# ATtiny84LEDEL.net
KiCad netlist of a schematic drawn in EAGLE
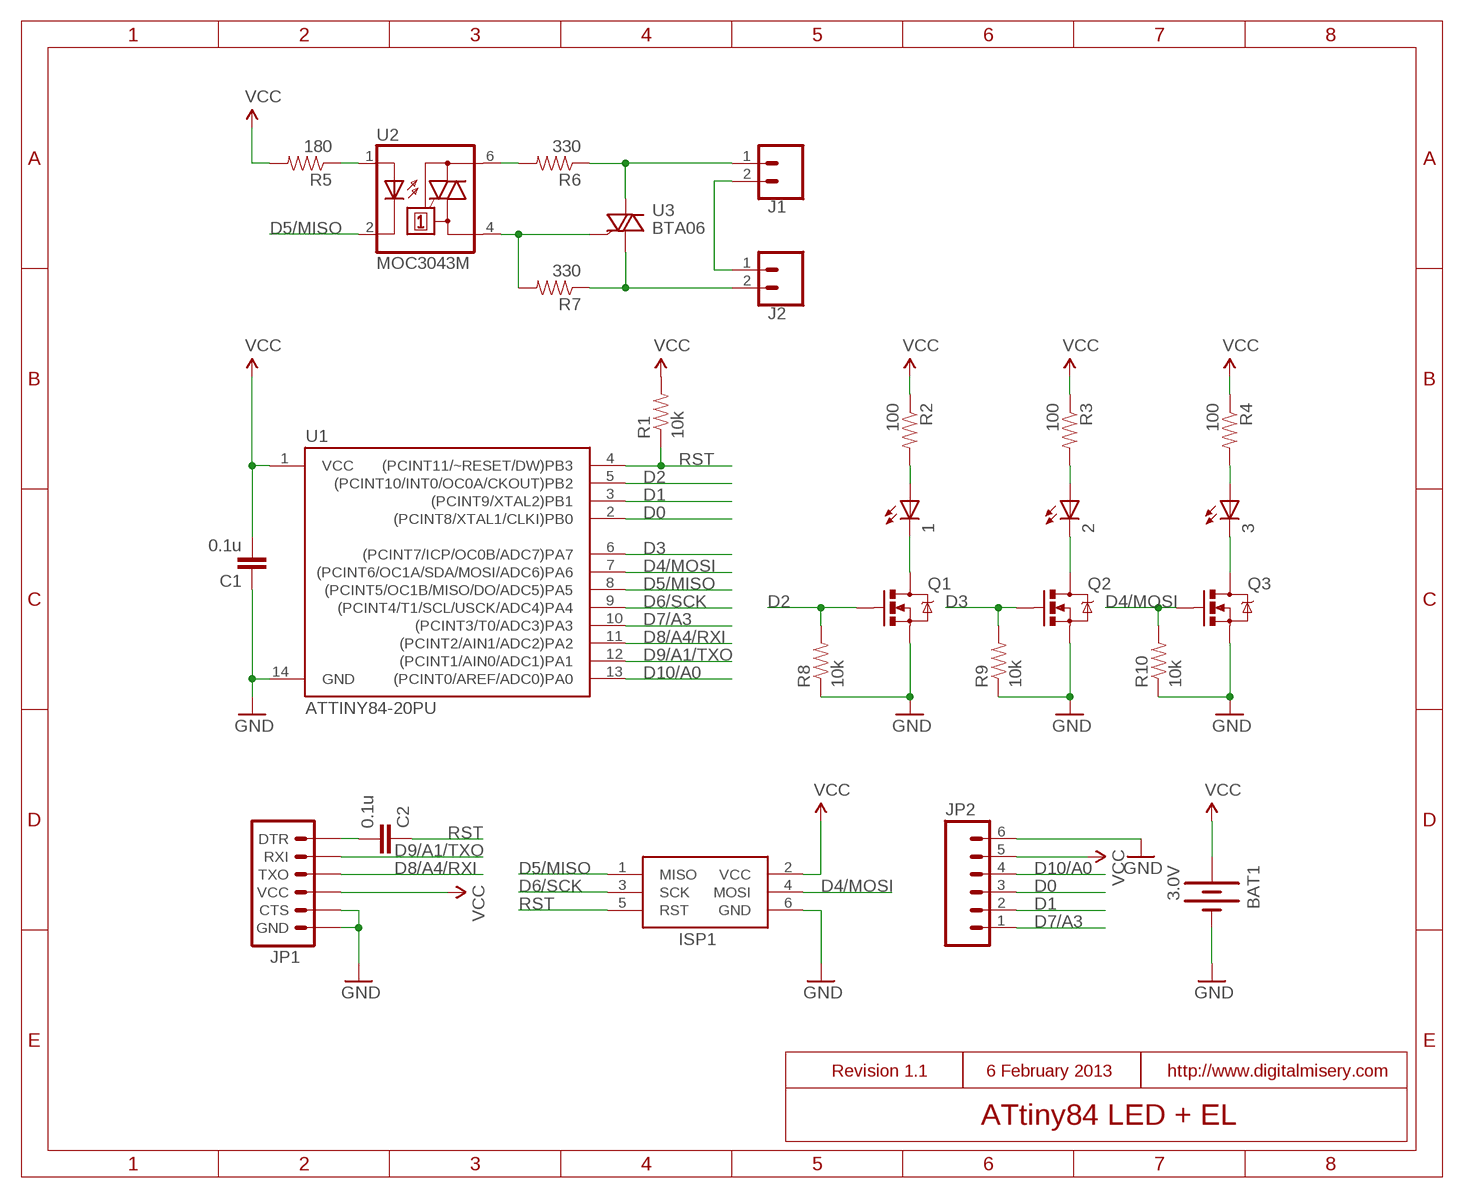
[diagram p0: schematic, sheet 1]

(export (version "E")
  (design (tool "Eeschema 10.0.6"))
  (components
    (comp (ref "1")
      (value "LED5MM")
      (footprint "eagle-import:LED5MM")
      (libsource (lib "eagle-import") (part "LED5MM"))
    )
    (comp (ref "2")
      (value "LED5MM")
      (footprint "eagle-import:LED5MM")
      (libsource (lib "eagle-import") (part "LED5MM"))
    )
    (comp (ref "3")
      (value "LED5MM")
      (footprint "eagle-import:LED5MM")
      (libsource (lib "eagle-import") (part "LED5MM"))
    )
    (comp (ref "BAT1")
      (value "3.0V")
      (footprint "eagle-import:JEELABS_BATTCOM_20MM_PTH")
      (libsource (lib "eagle-import") (part "JEELABS_BATTERY20PTH"))
    )
    (comp (ref "C1")
      (value "0.1u")
      (footprint "eagle-import:CAP-PTH-SMALL")
      (libsource (lib "eagle-import") (part "CAPPTH"))
    )
    (comp (ref "C2")
      (value "0.1u")
      (footprint "eagle-import:CAP-PTH-SMALL")
      (libsource (lib "eagle-import") (part "CAPPTH"))
    )
    (comp (ref "ISP1")
      (value "AVRISP-6")
      (footprint "eagle-import:AVRISP")
      (libsource (lib "eagle-import") (part "AVRISP-6"))
    )
    (comp (ref "J1")
      (value "M025MM")
      (footprint "eagle-import:SCREWTERMINAL-5MM-2")
      (libsource (lib "eagle-import") (part "M025MM"))
    )
    (comp (ref "J2")
      (value "M025MM")
      (footprint "eagle-import:SCREWTERMINAL-5MM-2")
      (libsource (lib "eagle-import") (part "M025MM"))
    )
    (comp (ref "JP1")
      (value "ARDUINO_SERIAL_PROGRAMLONGPADS")
      (footprint "eagle-import:1X06_LONGPADS")
      (libsource (lib "eagle-import") (part "ARDUINO_SERIAL_PROGRAMLONGPADS"))
    )
    (comp (ref "JP2")
      (value "M06LONGPADS")
      (footprint "eagle-import:1X06_LONGPADS")
      (libsource (lib "eagle-import") (part "M06LONGPADS"))
    )
    (comp (ref "Q1")
      (value "MOSFET-NCHANNELPTH")
      (footprint "eagle-import:TO-92")
      (libsource (lib "eagle-import") (part "MOSFET-NCHANNELPTH"))
    )
    (comp (ref "Q2")
      (value "MOSFET-NCHANNELPTH")
      (footprint "eagle-import:TO-92")
      (libsource (lib "eagle-import") (part "MOSFET-NCHANNELPTH"))
    )
    (comp (ref "Q3")
      (value "MOSFET-NCHANNELPTH")
      (footprint "eagle-import:TO-92")
      (libsource (lib "eagle-import") (part "MOSFET-NCHANNELPTH"))
    )
    (comp (ref "R1")
      (value "10k")
      (footprint "eagle-import:AXIAL-0.4")
      (libsource (lib "eagle-import") (part "RESISTORPTH-1/4W"))
    )
    (comp (ref "R2")
      (value "100")
      (footprint "eagle-import:AXIAL-0.4")
      (libsource (lib "eagle-import") (part "RESISTORPTH-1/4W"))
    )
    (comp (ref "R3")
      (value "100")
      (footprint "eagle-import:AXIAL-0.4")
      (libsource (lib "eagle-import") (part "RESISTORPTH-1/4W"))
    )
    (comp (ref "R4")
      (value "100")
      (footprint "eagle-import:AXIAL-0.4")
      (libsource (lib "eagle-import") (part "RESISTORPTH-1/4W"))
    )
    (comp (ref "R5")
      (value "180")
      (footprint "eagle-import:AXIAL-0.4")
      (libsource (lib "eagle-import") (part "RESISTORPTH-1/4W"))
    )
    (comp (ref "R6")
      (value "330")
      (footprint "eagle-import:AXIAL-0.4")
      (libsource (lib "eagle-import") (part "RESISTORPTH-1/4W"))
    )
    (comp (ref "R7")
      (value "330")
      (footprint "eagle-import:AXIAL-0.4")
      (libsource (lib "eagle-import") (part "RESISTORPTH-1/4W"))
    )
    (comp (ref "R8")
      (value "10k")
      (footprint "eagle-import:AXIAL-0.4")
      (libsource (lib "eagle-import") (part "RESISTORPTH-1/4W"))
    )
    (comp (ref "R9")
      (value "10k")
      (footprint "eagle-import:AXIAL-0.4")
      (libsource (lib "eagle-import") (part "RESISTORPTH-1/4W"))
    )
    (comp (ref "R10")
      (value "10k")
      (footprint "eagle-import:AXIAL-0.4")
      (libsource (lib "eagle-import") (part "RESISTORPTH-1/4W"))
    )
    (comp (ref "U1")
      (value "ATTINY84-20PU")
      (footprint "eagle-import:DIL14")
      (libsource (lib "eagle-import") (part "ATTINY84ATTINY84-20PU"))
    )
    (comp (ref "U2")
      (value "MOC3043M")
      (footprint "eagle-import:DIL06")
      (fields (field (name "MF") "FAIRCHILD SEMICONDUCTOR") (field (name "MPN") "MOC3043-M"))
      (libsource (lib "eagle-import") (part "MOC3043M"))
    )
    (comp (ref "U3")
      (value "BTA06")
      (footprint "eagle-import:TO220AB")
      (libsource (lib "eagle-import") (part "BTA06"))
    )
  )
  (nets
    (net (code "1") (name "/D0") (class "Default")
      (node (ref "JP2") (pin "3") (pinfunction "3_3") (pintype "passive"))
      (node (ref "U1") (pin "2") (pinfunction "(PCINT8/XTAL1/CLKI)PB0_2") (pintype "bidirectional"))
    )
    (net (code "2") (name "/D1") (class "Default")
      (node (ref "JP2") (pin "2") (pinfunction "2_2") (pintype "passive"))
      (node (ref "U1") (pin "3") (pinfunction "(PCINT9/XTAL2)PB1_3") (pintype "bidirectional"))
    )
    (net (code "3") (name "/D2") (class "Default")
      (node (ref "Q1") (pin "2") (pinfunction "G_2") (pintype "passive"))
      (node (ref "R8") (pin "P$2") (pinfunction "2_P$2") (pintype "passive"))
      (node (ref "U1") (pin "5") (pinfunction "(PCINT10/INT0/OC0A/CKOUT)PB2_5") (pintype "bidirectional"))
    )
    (net (code "4") (name "/D3") (class "Default")
      (node (ref "Q2") (pin "2") (pinfunction "G_2") (pintype "passive"))
      (node (ref "R9") (pin "P$2") (pinfunction "2_P$2") (pintype "passive"))
      (node (ref "U1") (pin "6") (pinfunction "(PCINT7/ICP/OC0B/ADC7)PA7_6") (pintype "bidirectional"))
    )
    (net (code "5") (name "/D4{slash}MOSI") (class "Default")
      (node (ref "ISP1") (pin "4") (pinfunction "MOSI_4") (pintype "output"))
      (node (ref "Q3") (pin "2") (pinfunction "G_2") (pintype "passive"))
      (node (ref "R10") (pin "P$2") (pinfunction "2_P$2") (pintype "passive"))
      (node (ref "U1") (pin "7") (pinfunction "(PCINT6/OC1A/SDA/MOSI/ADC6)PA6_7") (pintype "bidirectional"))
    )
    (net (code "6") (name "/D5{slash}MISO") (class "Default")
      (node (ref "ISP1") (pin "1") (pinfunction "MISO_1") (pintype "input"))
      (node (ref "U1") (pin "8") (pinfunction "(PCINT5/OC1B/MISO/DO/ADC5)PA5_8") (pintype "bidirectional"))
      (node (ref "U2") (pin "2") (pinfunction "C_2") (pintype "passive"))
    )
    (net (code "7") (name "/D6{slash}SCK") (class "Default")
      (node (ref "ISP1") (pin "3") (pinfunction "SCK_3") (pintype "output"))
      (node (ref "U1") (pin "9") (pinfunction "(PCINT4/T1/SCL/USCK/ADC4)PA4_9") (pintype "bidirectional"))
    )
    (net (code "8") (name "/D7{slash}A3") (class "Default")
      (node (ref "JP2") (pin "1") (pinfunction "1_1") (pintype "passive"))
      (node (ref "U1") (pin "10") (pinfunction "(PCINT3/T0/ADC3)PA3_10") (pintype "bidirectional"))
    )
    (net (code "9") (name "/D8{slash}A4{slash}RXI") (class "Default")
      (node (ref "JP1") (pin "3") (pinfunction "TXO_3") (pintype "passive"))
      (node (ref "U1") (pin "11") (pinfunction "(PCINT2/AIN1/ADC2)PA2_11") (pintype "bidirectional"))
    )
    (net (code "10") (name "/D9{slash}A1{slash}TXO") (class "Default")
      (node (ref "JP1") (pin "2") (pinfunction "RXI_2") (pintype "passive"))
      (node (ref "U1") (pin "12") (pinfunction "(PCINT1/AIN0/ADC1)PA1_12") (pintype "bidirectional"))
    )
    (net (code "11") (name "/D10{slash}A0") (class "Default")
      (node (ref "JP2") (pin "4") (pinfunction "4_4") (pintype "passive"))
      (node (ref "U1") (pin "13") (pinfunction "(PCINT0/AREF/ADC0)PA0_13") (pintype "bidirectional"))
    )
    (net (code "12") (name "/RST") (class "Default")
      (node (ref "C2") (pin "1") (pinfunction "1_1") (pintype "passive"))
      (node (ref "ISP1") (pin "5") (pinfunction "RST_5") (pintype "output"))
      (node (ref "R1") (pin "P$1") (pinfunction "1_P$1") (pintype "passive"))
      (node (ref "U1") (pin "4") (pinfunction "(PCINT11/~{RESET/DW})PB3_4") (pintype "bidirectional"))
    )
    (net (code "13") (name "GND") (class "Default")
      (node (ref "BAT1") (pin "2") (pinfunction "-_2") (pintype "power_in"))
      (node (ref "C1") (pin "1") (pinfunction "1_1") (pintype "passive"))
      (node (ref "ISP1") (pin "6") (pinfunction "GND_6") (pintype "power_in"))
      (node (ref "JP1") (pin "5") (pinfunction "CTS_5") (pintype "passive"))
      (node (ref "JP1") (pin "6") (pinfunction "GND_6") (pintype "passive"))
      (node (ref "JP2") (pin "6") (pinfunction "6_6") (pintype "passive"))
      (node (ref "Q1") (pin "3") (pinfunction "S_3") (pintype "passive"))
      (node (ref "Q2") (pin "3") (pinfunction "S_3") (pintype "passive"))
      (node (ref "Q3") (pin "3") (pinfunction "S_3") (pintype "passive"))
      (node (ref "R10") (pin "P$1") (pinfunction "1_P$1") (pintype "passive"))
      (node (ref "R8") (pin "P$1") (pinfunction "1_P$1") (pintype "passive"))
      (node (ref "R9") (pin "P$1") (pinfunction "1_P$1") (pintype "passive"))
      (node (ref "U1") (pin "14") (pinfunction "GND_14") (pintype "bidirectional"))
    )
    (net (code "14") (name "Net-(1-C)") (class "Default")
      (node (ref "1") (pin "K") (pinfunction "C_K") (pintype "passive"))
      (node (ref "Q1") (pin "1") (pinfunction "D_1") (pintype "passive"))
    )
    (net (code "15") (name "Net-(2-C)") (class "Default")
      (node (ref "2") (pin "K") (pinfunction "C_K") (pintype "passive"))
      (node (ref "Q2") (pin "1") (pinfunction "D_1") (pintype "passive"))
    )
    (net (code "16") (name "Net-(3-C)") (class "Default")
      (node (ref "3") (pin "K") (pinfunction "C_K") (pintype "passive"))
      (node (ref "Q3") (pin "1") (pinfunction "D_1") (pintype "passive"))
    )
    (net (code "17") (name "Net-(J1-Pad2)") (class "Default")
      (node (ref "J1") (pin "2") (pinfunction "2_2") (pintype "passive"))
      (node (ref "J2") (pin "1") (pinfunction "1_1") (pintype "passive"))
    )
    (net (code "18") (name "Net-(JP1-DTR)") (class "Default")
      (node (ref "C2") (pin "2") (pinfunction "2_2") (pintype "passive"))
      (node (ref "JP1") (pin "1") (pinfunction "DTR_1") (pintype "passive"))
    )
    (net (code "19") (name "Net-(R2-2)") (class "Default")
      (node (ref "1") (pin "A") (pinfunction "A_A") (pintype "passive"))
      (node (ref "R2") (pin "P$2") (pinfunction "2_P$2") (pintype "passive"))
    )
    (net (code "20") (name "Net-(R3-2)") (class "Default")
      (node (ref "2") (pin "A") (pinfunction "A_A") (pintype "passive"))
      (node (ref "R3") (pin "P$2") (pinfunction "2_P$2") (pintype "passive"))
    )
    (net (code "21") (name "Net-(R4-2)") (class "Default")
      (node (ref "3") (pin "A") (pinfunction "A_A") (pintype "passive"))
      (node (ref "R4") (pin "P$2") (pinfunction "2_P$2") (pintype "passive"))
    )
    (net (code "22") (name "Net-(R5-1)") (class "Default")
      (node (ref "R5") (pin "P$1") (pinfunction "1_P$1") (pintype "passive"))
      (node (ref "U2") (pin "1") (pinfunction "A_1") (pintype "passive"))
    )
    (net (code "23") (name "Net-(R6-1)") (class "Default")
      (node (ref "J1") (pin "1") (pinfunction "1_1") (pintype "passive"))
      (node (ref "R6") (pin "P$1") (pinfunction "1_P$1") (pintype "passive"))
      (node (ref "U3") (pin "2") (pinfunction "A2_2") (pintype "passive"))
    )
    (net (code "24") (name "Net-(R6-2)") (class "Default")
      (node (ref "R6") (pin "P$2") (pinfunction "2_P$2") (pintype "passive"))
      (node (ref "U2") (pin "6") (pinfunction "A2_6") (pintype "passive"))
    )
    (net (code "25") (name "Net-(R7-1)") (class "Default")
      (node (ref "J2") (pin "2") (pinfunction "2_2") (pintype "passive"))
      (node (ref "R7") (pin "P$1") (pinfunction "1_P$1") (pintype "passive"))
      (node (ref "U3") (pin "1") (pinfunction "A1_1") (pintype "passive"))
    )
    (net (code "26") (name "Net-(R7-2)") (class "Default")
      (node (ref "R7") (pin "P$2") (pinfunction "2_P$2") (pintype "passive"))
      (node (ref "U2") (pin "4") (pinfunction "A1_4") (pintype "passive"))
      (node (ref "U3") (pin "3") (pinfunction "G_3") (pintype "passive"))
    )
    (net (code "27") (name "VCC") (class "Default")
      (node (ref "BAT1") (pin "1") (pinfunction "+_1") (pintype "power_in"))
      (node (ref "C1") (pin "2") (pinfunction "2_2") (pintype "passive"))
      (node (ref "ISP1") (pin "2") (pinfunction "VCC_2") (pintype "power_in"))
      (node (ref "JP1") (pin "4") (pinfunction "VCC_4") (pintype "passive"))
      (node (ref "JP2") (pin "5") (pinfunction "5_5") (pintype "passive"))
      (node (ref "R1") (pin "P$2") (pinfunction "2_P$2") (pintype "passive"))
      (node (ref "R2") (pin "P$1") (pinfunction "1_P$1") (pintype "passive"))
      (node (ref "R3") (pin "P$1") (pinfunction "1_P$1") (pintype "passive"))
      (node (ref "R4") (pin "P$1") (pinfunction "1_P$1") (pintype "passive"))
      (node (ref "R5") (pin "P$2") (pinfunction "2_P$2") (pintype "passive"))
      (node (ref "U1") (pin "1") (pinfunction "VCC_1") (pintype "bidirectional"))
    )
  )
)
